# push_button.net
KiCad netlist of a schematic drawn in Altium Designer
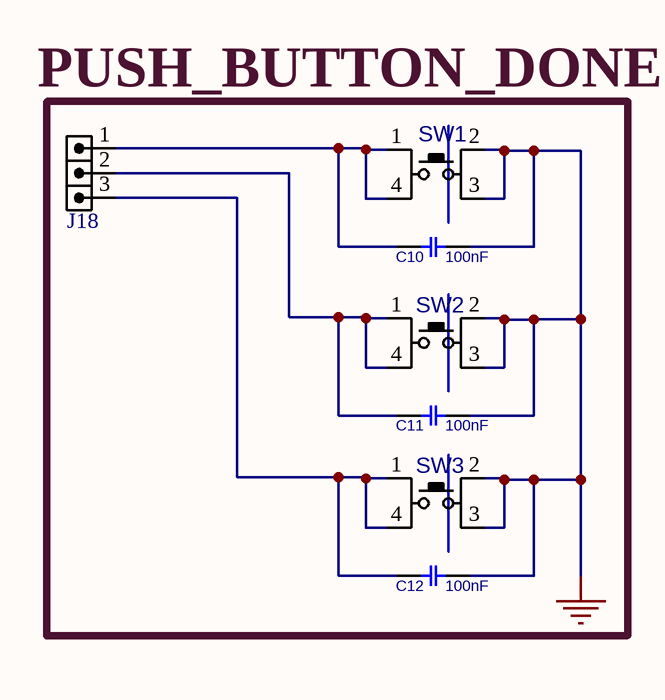
[diagram p0: push_button.SchDoc]

(export (version "E")
  (design (tool "Eeschema 10.0.6"))
  (components
    (comp (ref "C10")
      (value "100nF")
      (footprint "C_CER_D3")
      (description "CAP, THD, CER MULTI LAYER,")
      (fields (field (name "MANF_P#") "MANF_PART#") (field (name "MANF") "MANF"))
      (libsource (lib "AvrDevelopmentBoard") (part "CAP_THD_CERML"))
    )
    (comp (ref "C11")
      (value "100nF")
      (footprint "C_CER_D3")
      (description "CAP, THD, CER MULTI LAYER,")
      (fields (field (name "MANF_P#") "MANF_PART#") (field (name "MANF") "MANF"))
      (libsource (lib "AvrDevelopmentBoard") (part "CAP_THD_CERML"))
    )
    (comp (ref "C12")
      (value "100nF")
      (footprint "C_CER_D3")
      (description "CAP, THD, CER MULTI LAYER,")
      (fields (field (name "MANF_P#") "MANF_PART#") (field (name "MANF") "MANF"))
      (libsource (lib "AvrDevelopmentBoard") (part "CAP_THD_CERML"))
    )
    (comp (ref "J18")
      (value "HDRMINI_3")
      (footprint "HDRMINI_M_1X3")
      (description "CONN, HEADER, Male, pitch: 1.27mm, 3POS")
      (libsource (lib "conn_header_1.27mm_st") (part "HDRMINI_M_1X3"))
    )
    (comp (ref "SW1")
      (value "PUSHBUTTON")
      (footprint "SWPBT_SPDT_6X6X5")
      (description "SWITCH, PUSH BUTTON, TACTILE, THD, SPDT, 4X4MM")
      (libsource (lib "switch_tact_PUSHB") (part "SWPBT_SPDT_6X6X5"))
    )
    (comp (ref "SW2")
      (value "PUSHBUTTON")
      (footprint "SWPBT_SPDT_6X6X5")
      (description "SWITCH, PUSH BUTTON, TACTILE, THD, SPDT, 4X4MM")
      (libsource (lib "switch_tact_PUSHB") (part "SWPBT_SPDT_6X6X5"))
    )
    (comp (ref "SW3")
      (value "PUSHBUTTON")
      (footprint "SWPBT_SPDT_6X6X5")
      (description "SWITCH, PUSH BUTTON, TACTILE, THD, SPDT, 4X4MM")
      (libsource (lib "switch_tact_PUSHB") (part "SWPBT_SPDT_6X6X5"))
    )
  )
  (nets
    (net (code "1") (name "GND") (class "Default")
      (node (ref "C10") (pin "2") (pinfunction "2_2") (pintype "passive"))
      (node (ref "C11") (pin "2") (pinfunction "2_2") (pintype "passive"))
      (node (ref "C12") (pin "2") (pinfunction "2_2") (pintype "passive"))
      (node (ref "SW1") (pin "2") (pinfunction "P3_2") (pintype "passive"))
      (node (ref "SW1") (pin "3") (pinfunction "P4_3") (pintype "passive"))
      (node (ref "SW2") (pin "2") (pinfunction "P3_2") (pintype "passive"))
      (node (ref "SW2") (pin "3") (pinfunction "P4_3") (pintype "passive"))
      (node (ref "SW3") (pin "2") (pinfunction "P3_2") (pintype "passive"))
      (node (ref "SW3") (pin "3") (pinfunction "P4_3") (pintype "passive"))
    )
    (net (code "2") (name "Net-(SW1-P1)") (class "Default")
      (node (ref "C10") (pin "1") (pinfunction "1_1") (pintype "passive"))
      (node (ref "J18") (pin "1") (pinfunction "1_1") (pintype "passive"))
      (node (ref "SW1") (pin "1") (pinfunction "P1_1") (pintype "passive"))
      (node (ref "SW1") (pin "4") (pinfunction "P2_4") (pintype "passive"))
    )
    (net (code "3") (name "Net-(SW2-P1)") (class "Default")
      (node (ref "C11") (pin "1") (pinfunction "1_1") (pintype "passive"))
      (node (ref "J18") (pin "2") (pinfunction "2_2") (pintype "passive"))
      (node (ref "SW2") (pin "1") (pinfunction "P1_1") (pintype "passive"))
      (node (ref "SW2") (pin "4") (pinfunction "P2_4") (pintype "passive"))
    )
    (net (code "4") (name "Net-(SW3-P1)") (class "Default")
      (node (ref "C12") (pin "1") (pinfunction "1_1") (pintype "passive"))
      (node (ref "J18") (pin "3") (pinfunction "3_3") (pintype "passive"))
      (node (ref "SW3") (pin "1") (pinfunction "P1_1") (pintype "passive"))
      (node (ref "SW3") (pin "4") (pinfunction "P2_4") (pintype "passive"))
    )
  )
)
